# Sensor_AFE_Explorer_Rev2.net
KiCad netlist of a schematic drawn in EAGLE
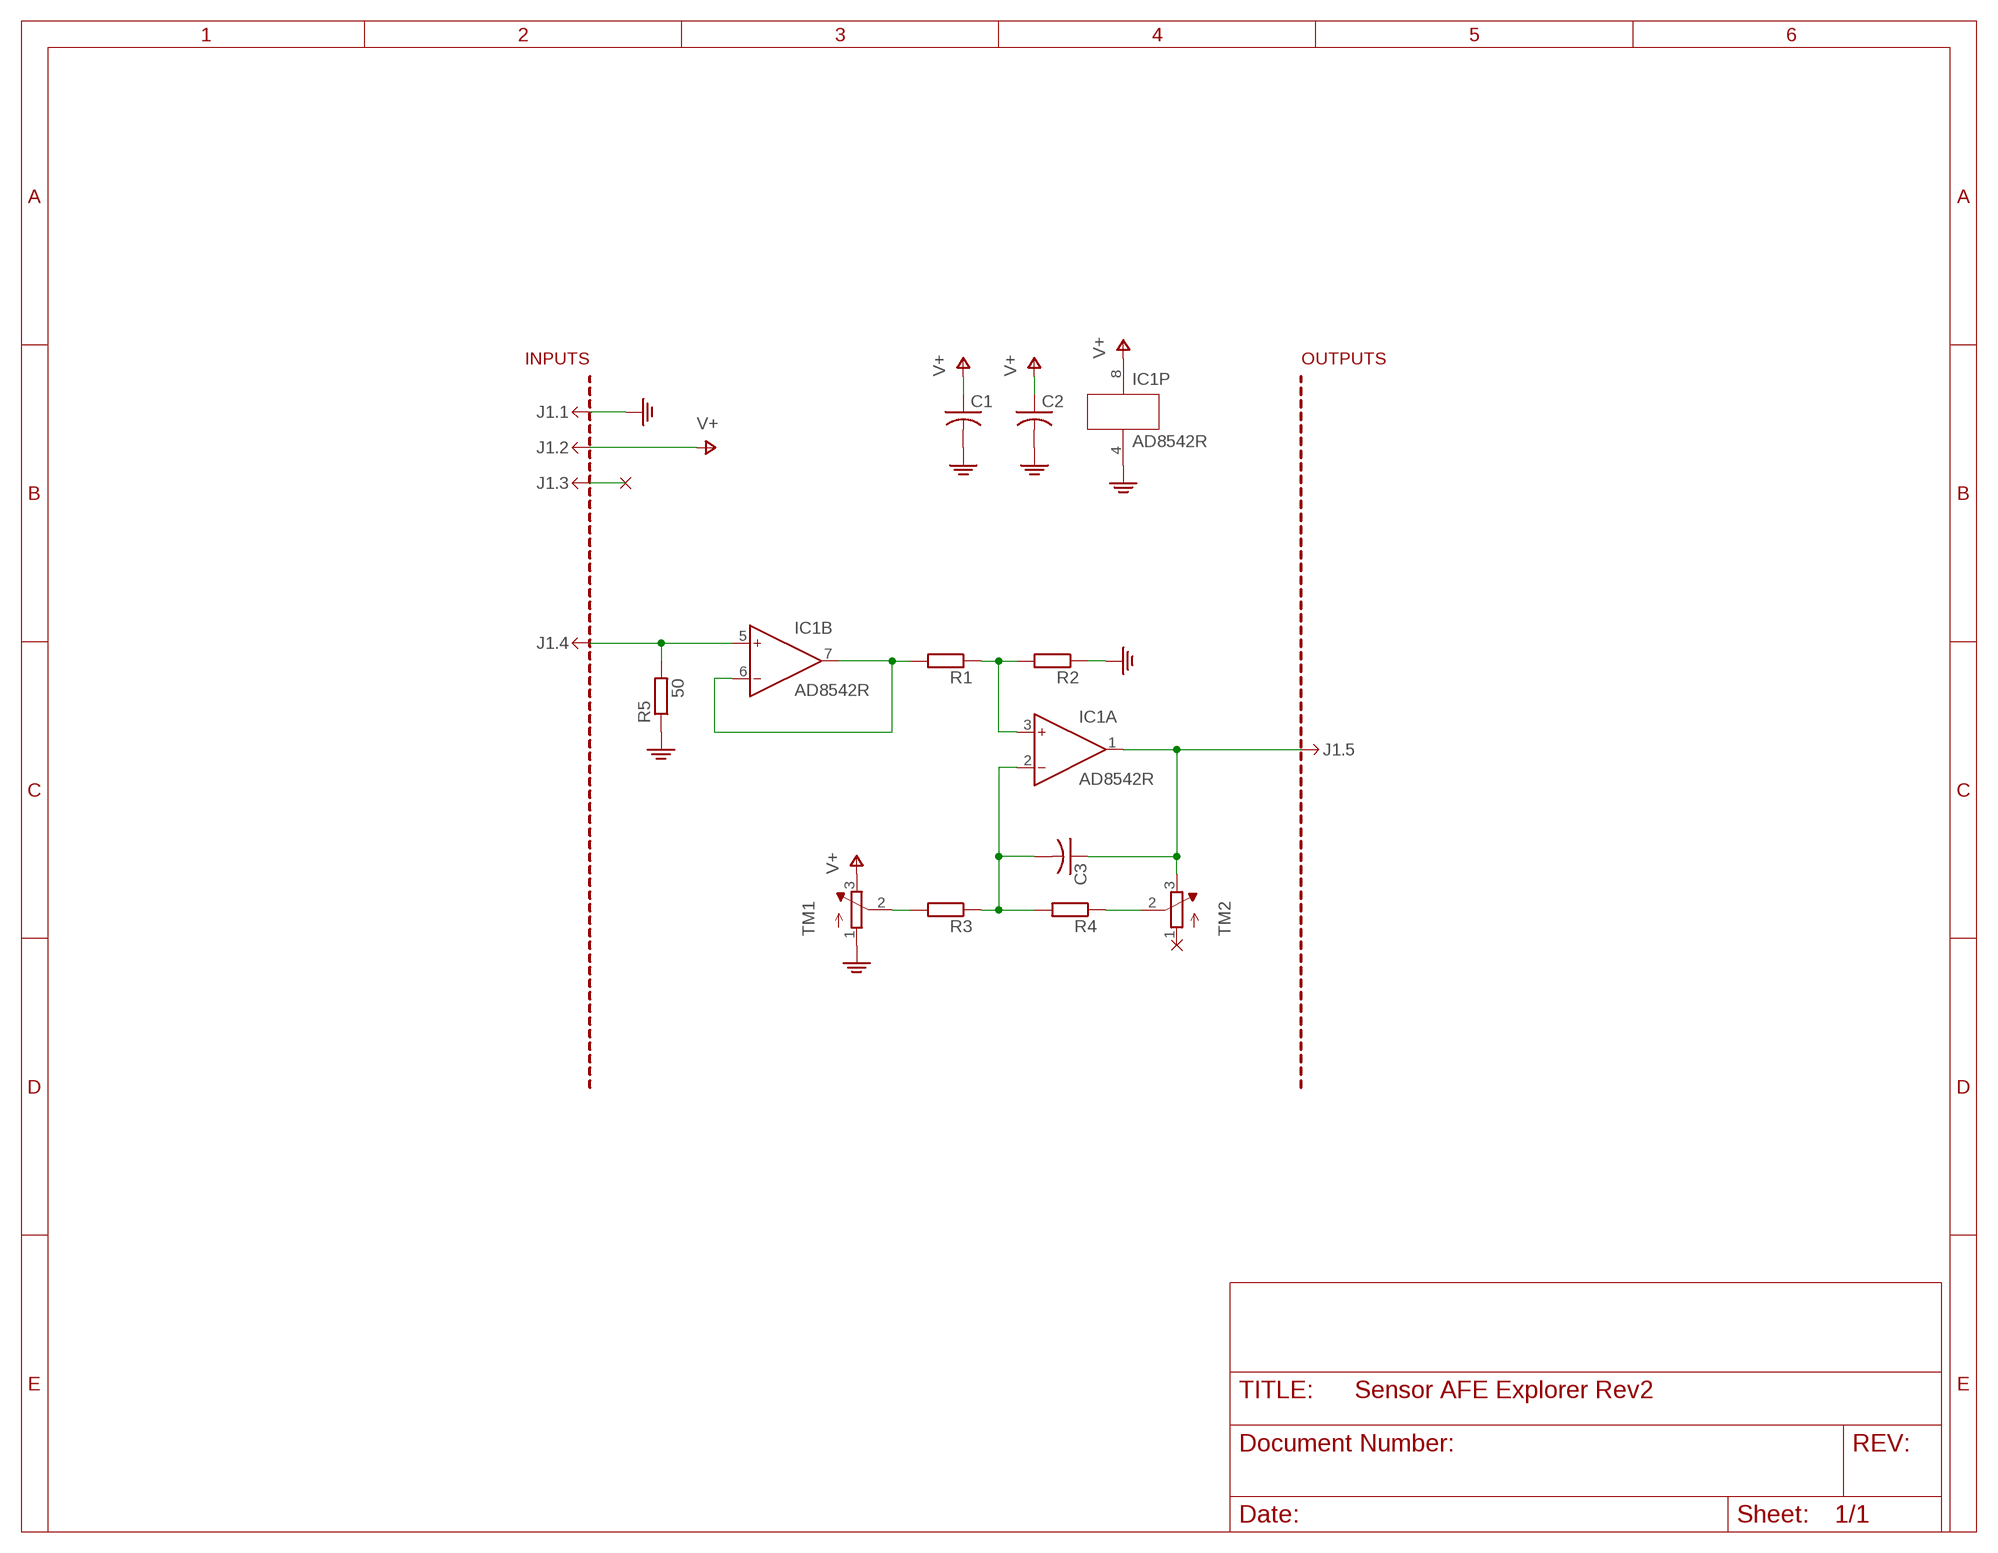
[diagram p0: schematic, sheet 1]

(export (version "E")
  (design (tool "Eeschema 10.0.6"))
  (components
    (comp (ref "C1")
      (value "C-USC0805")
      (footprint "eagle-import:C0805")
      (libsource (lib "eagle-import") (part "C-USC0805"))
    )
    (comp (ref "C2")
      (value "C-USC0805")
      (footprint "eagle-import:C0805")
      (libsource (lib "eagle-import") (part "C-USC0805"))
    )
    (comp (ref "C3")
      (value "C-USC0805")
      (footprint "eagle-import:C0805")
      (libsource (lib "eagle-import") (part "C-USC0805"))
    )
    (comp (ref "IC1")
      (value "AD8542R")
      (footprint "eagle-import:SO8")
      (fields (field (name "MF") "ALTERA CORPORATION") (field (name "MPN") "AD8542ARZ-REEL"))
      (libsource (lib "eagle-import") (part "AD8542R"))
    )
    (comp (ref "J1.")
      (value "MINIPCB_5P50X50")
      (footprint "eagle-import:MINIPCB_50X50MM")
      (fields (field (name "PART_NUMBER") "AFE Explorer") (field (name "REVISION") "2"))
      (libsource (lib "eagle-import") (part "MINIPCB_5P50X50"))
    )
    (comp (ref "R1")
      (value "RESISTORSMD")
      (footprint "eagle-import:R0805")
      (libsource (lib "eagle-import") (part "RESISTORSMD"))
    )
    (comp (ref "R2")
      (value "RESISTORSMD")
      (footprint "eagle-import:R0805")
      (libsource (lib "eagle-import") (part "RESISTORSMD"))
    )
    (comp (ref "R3")
      (value "RESISTORSMD")
      (footprint "eagle-import:R0805")
      (libsource (lib "eagle-import") (part "RESISTORSMD"))
    )
    (comp (ref "R4")
      (value "RESISTORSMD")
      (footprint "eagle-import:R0805")
      (libsource (lib "eagle-import") (part "RESISTORSMD"))
    )
    (comp (ref "R5")
      (value "50")
      (footprint "eagle-import:R0805")
      (libsource (lib "eagle-import") (part "RESISTORSMD"))
    )
    (comp (ref "TM1")
      (value "TRIMPOT3386")
      (footprint "eagle-import:TRIM-3386")
      (libsource (lib "eagle-import") (part "TRIMPOT3386"))
    )
    (comp (ref "TM2")
      (value "TRIMPOT3386")
      (footprint "eagle-import:TRIM-3386")
      (libsource (lib "eagle-import") (part "TRIMPOT3386"))
    )
  )
  (nets
    (net (code "1") (name "GND") (class "Default")
      (node (ref "C1") (pin "2") (pinfunction "2_2") (pintype "passive"))
      (node (ref "C2") (pin "2") (pinfunction "2_2") (pintype "passive"))
      (node (ref "IC1") (pin "4") (pinfunction "V-_4") (pintype "power_in"))
      (node (ref "J1.") (pin "1") (pinfunction "1_1") (pintype "bidirectional"))
      (node (ref "R2") (pin "1") (pinfunction "1_1") (pintype "passive"))
      (node (ref "R5") (pin "1") (pinfunction "1_1") (pintype "passive"))
      (node (ref "TM1") (pin "1") (pinfunction "A_1") (pintype "passive"))
    )
    (net (code "2") (name "Net-(IC1A-IN+)") (class "Default")
      (node (ref "IC1") (pin "3") (pinfunction "IN+_3") (pintype "input"))
      (node (ref "R1") (pin "1") (pinfunction "1_1") (pintype "passive"))
      (node (ref "R2") (pin "2") (pinfunction "2_2") (pintype "passive"))
    )
    (net (code "3") (name "Net-(IC1A-IN-)") (class "Default")
      (node (ref "C3") (pin "2") (pinfunction "2_2") (pintype "passive"))
      (node (ref "IC1") (pin "2") (pinfunction "IN-_2") (pintype "input"))
      (node (ref "R3") (pin "1") (pinfunction "1_1") (pintype "passive"))
      (node (ref "R4") (pin "2") (pinfunction "2_2") (pintype "passive"))
    )
    (net (code "4") (name "Net-(IC1A-OUT)") (class "Default")
      (node (ref "C3") (pin "1") (pinfunction "1_1") (pintype "passive"))
      (node (ref "IC1") (pin "1") (pinfunction "OUT_1") (pintype "output"))
      (node (ref "J1.") (pin "5") (pinfunction "1_5") (pintype "bidirectional"))
      (node (ref "TM2") (pin "3") (pinfunction "E_3") (pintype "passive"))
    )
    (net (code "5") (name "Net-(IC1B-IN+)") (class "Default")
      (node (ref "IC1") (pin "5") (pinfunction "IN+_5") (pintype "input"))
      (node (ref "J1.") (pin "4") (pinfunction "1_4") (pintype "bidirectional"))
      (node (ref "R5") (pin "2") (pinfunction "2_2") (pintype "passive"))
    )
    (net (code "6") (name "Net-(IC1B-IN-)") (class "Default")
      (node (ref "IC1") (pin "6") (pinfunction "IN-_6") (pintype "input"))
      (node (ref "IC1") (pin "7") (pinfunction "OUT_7") (pintype "output"))
      (node (ref "R1") (pin "2") (pinfunction "2_2") (pintype "passive"))
    )
    (net (code "7") (name "Net-(TM1-S)") (class "Default")
      (node (ref "R3") (pin "2") (pinfunction "2_2") (pintype "passive"))
      (node (ref "TM1") (pin "2") (pinfunction "S_2") (pintype "passive"))
    )
    (net (code "8") (name "Net-(TM2-S)") (class "Default")
      (node (ref "R4") (pin "1") (pinfunction "1_1") (pintype "passive"))
      (node (ref "TM2") (pin "2") (pinfunction "S_2") (pintype "passive"))
    )
    (net (code "9") (name "V+") (class "Default")
      (node (ref "C1") (pin "1") (pinfunction "1_1") (pintype "passive"))
      (node (ref "C2") (pin "1") (pinfunction "1_1") (pintype "passive"))
      (node (ref "IC1") (pin "8") (pinfunction "V+_8") (pintype "power_in"))
      (node (ref "J1.") (pin "2") (pinfunction "1_2") (pintype "bidirectional"))
      (node (ref "TM1") (pin "3") (pinfunction "E_3") (pintype "passive"))
    )
    (net (code "10") (name "unconnected-(J1.C-1-Pad3)") (class "Default")
      (node (ref "J1.") (pin "3") (pinfunction "1_3") (pintype "bidirectional"))
    )
    (net (code "11") (name "unconnected-(TM2-A-Pad1)") (class "Default")
      (node (ref "TM2") (pin "1") (pinfunction "A_1") (pintype "passive"))
    )
  )
)
